# 323ampV1.net
KiCad netlist of a schematic drawn in EAGLE
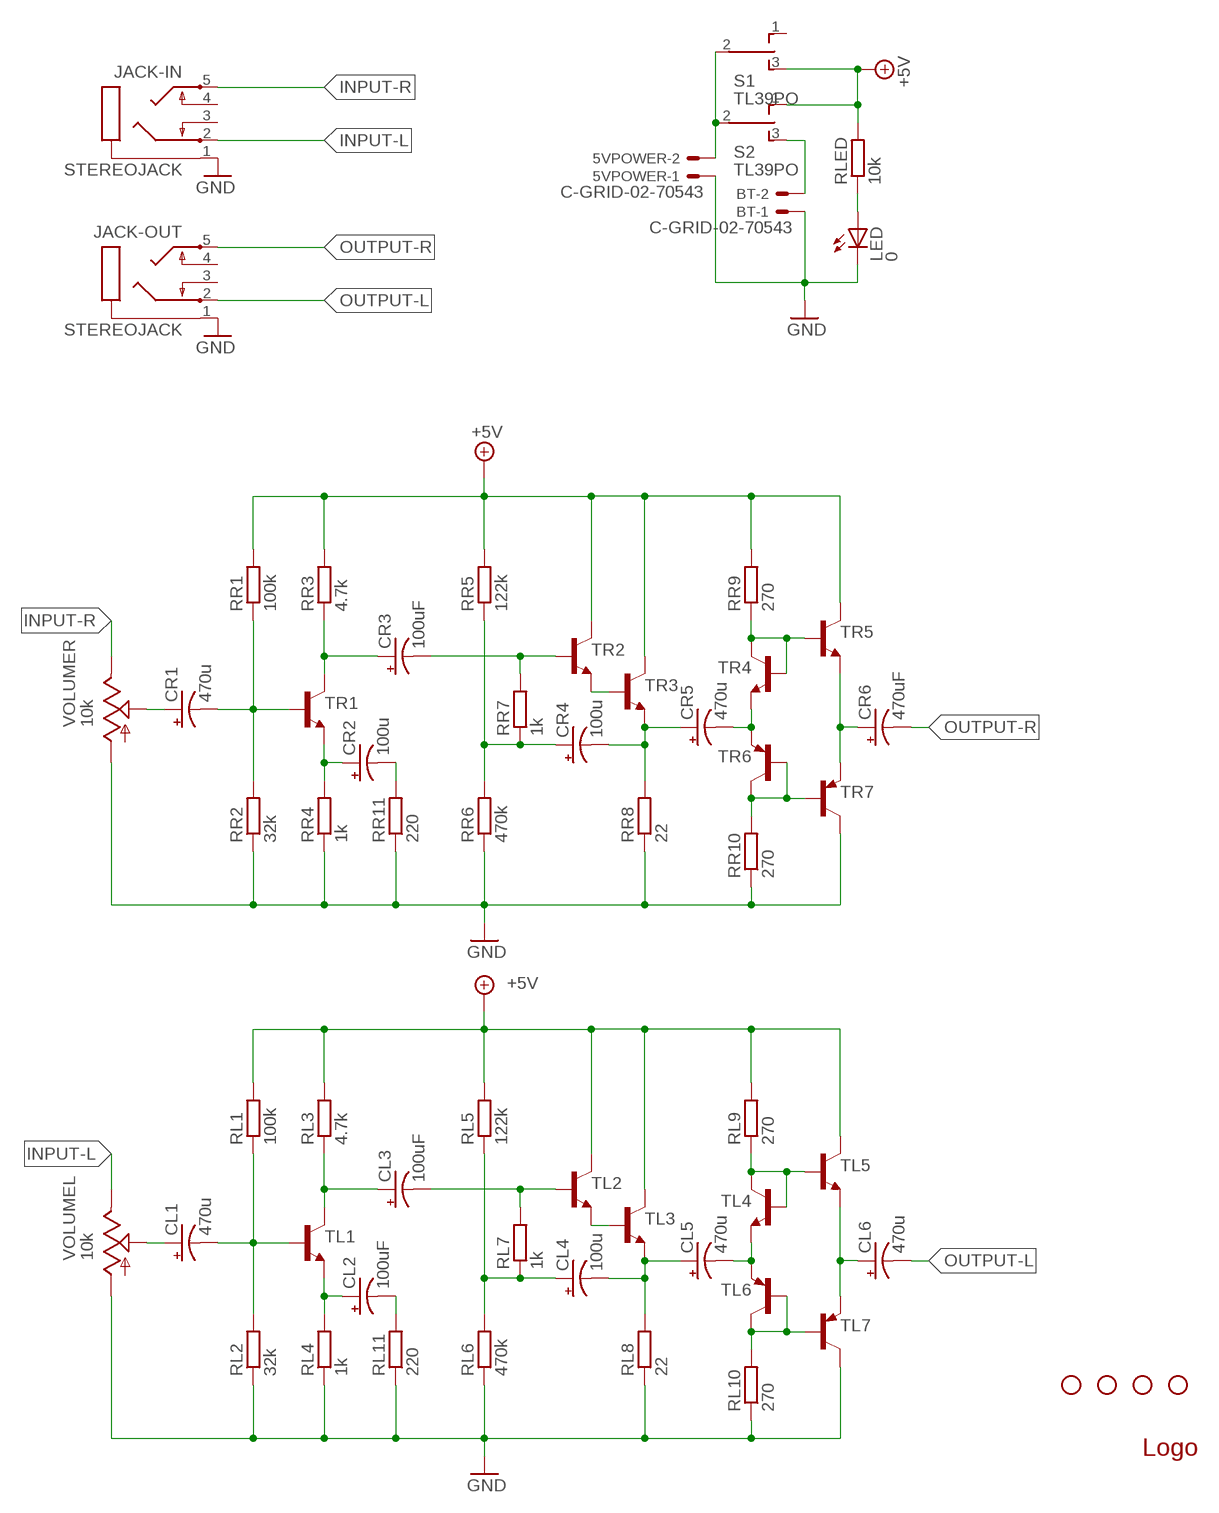
[diagram p0: schematic, sheet 1]

(export (version "E")
  (design (tool "Eeschema 10.0.6"))
  (components
    (comp (ref "5VPOWER")
      (value "C-GRID-02-70543")
      (footprint "eagle-import:70543-02")
      (libsource (lib "eagle-import") (part "C-GRID-02-70543"))
    )
    (comp (ref "BT")
      (value "C-GRID-02-70543")
      (footprint "eagle-import:70543-02")
      (libsource (lib "eagle-import") (part "C-GRID-02-70543"))
    )
    (comp (ref "CL1")
      (value "470u")
      (footprint "eagle-import:E2,5-6")
      (libsource (lib "eagle-import") (part "CPOL-USE2.5-6"))
    )
    (comp (ref "CL2")
      (value "100uF")
      (footprint "eagle-import:E2,5-6")
      (libsource (lib "eagle-import") (part "CPOL-USE2.5-6"))
    )
    (comp (ref "CL3")
      (value "100uF")
      (footprint "eagle-import:E2,5-6")
      (libsource (lib "eagle-import") (part "CPOL-USE2.5-6"))
    )
    (comp (ref "CL4")
      (value "100u")
      (footprint "eagle-import:E2,5-6")
      (libsource (lib "eagle-import") (part "CPOL-USE2.5-6"))
    )
    (comp (ref "CL5")
      (value "470u")
      (footprint "eagle-import:E2,5-6")
      (libsource (lib "eagle-import") (part "CPOL-USE2.5-6"))
    )
    (comp (ref "CL6")
      (value "470u")
      (footprint "eagle-import:E2,5-6")
      (libsource (lib "eagle-import") (part "CPOL-USE2.5-6"))
    )
    (comp (ref "CR1")
      (value "470u")
      (footprint "eagle-import:E2,5-6")
      (libsource (lib "eagle-import") (part "CPOL-USE2.5-6"))
    )
    (comp (ref "CR2")
      (value "100u")
      (footprint "eagle-import:E2,5-6")
      (libsource (lib "eagle-import") (part "CPOL-USE2.5-6"))
    )
    (comp (ref "CR3")
      (value "100uF")
      (footprint "eagle-import:E2,5-6")
      (libsource (lib "eagle-import") (part "CPOL-USE2.5-6"))
    )
    (comp (ref "CR4")
      (value "100u")
      (footprint "eagle-import:E2,5-6")
      (libsource (lib "eagle-import") (part "CPOL-USE2.5-6"))
    )
    (comp (ref "CR5")
      (value "470u")
      (footprint "eagle-import:E2,5-6")
      (libsource (lib "eagle-import") (part "CPOL-USE2.5-6"))
    )
    (comp (ref "CR6")
      (value "470uF")
      (footprint "eagle-import:E2,5-6")
      (libsource (lib "eagle-import") (part "CPOL-USE2.5-6"))
    )
    (comp (ref "JACK-IN")
      (value "STEREOJACK")
      (footprint "eagle-import:STX3100")
      (libsource (lib "eagle-import") (part "STEREOJACK"))
    )
    (comp (ref "JACK-OUT")
      (value "STEREOJACK")
      (footprint "eagle-import:STX3100")
      (libsource (lib "eagle-import") (part "STEREOJACK"))
    )
    (comp (ref "JP2")
      (value "STAND-OFF")
      (footprint "eagle-import:STAND-OFF")
      (libsource (lib "eagle-import") (part "STAND-OFF"))
    )
    (comp (ref "JP3")
      (value "STAND-OFF")
      (footprint "eagle-import:STAND-OFF")
      (libsource (lib "eagle-import") (part "STAND-OFF"))
    )
    (comp (ref "JP4")
      (value "STAND-OFF")
      (footprint "eagle-import:STAND-OFF")
      (libsource (lib "eagle-import") (part "STAND-OFF"))
    )
    (comp (ref "JP5")
      (value "STAND-OFF")
      (footprint "eagle-import:STAND-OFF")
      (libsource (lib "eagle-import") (part "STAND-OFF"))
    )
    (comp (ref "LED")
      (value "0")
      (footprint "eagle-import:LED3MM-MINUS")
      (libsource (lib "eagle-import") (part "LED-3MM-MINUS"))
    )
    (comp (ref "RL1")
      (value "100k")
      (footprint "eagle-import:0204_7")
      (libsource (lib "eagle-import") (part "R-EU_0204/7"))
    )
    (comp (ref "RL2")
      (value "32k")
      (footprint "eagle-import:0204_7")
      (libsource (lib "eagle-import") (part "R-EU_0204/7"))
    )
    (comp (ref "RL3")
      (value "4.7k")
      (footprint "eagle-import:0204_7")
      (libsource (lib "eagle-import") (part "R-EU_0204/7"))
    )
    (comp (ref "RL4")
      (value "1k")
      (footprint "eagle-import:0204_7")
      (libsource (lib "eagle-import") (part "R-EU_0204/7"))
    )
    (comp (ref "RL5")
      (value "122k")
      (footprint "eagle-import:0204_7")
      (libsource (lib "eagle-import") (part "R-EU_0204/7"))
    )
    (comp (ref "RL6")
      (value "470k")
      (footprint "eagle-import:0204_7")
      (libsource (lib "eagle-import") (part "R-EU_0204/7"))
    )
    (comp (ref "RL7")
      (value "1k")
      (footprint "eagle-import:0204_7")
      (libsource (lib "eagle-import") (part "R-EU_0204/7"))
    )
    (comp (ref "RL8")
      (value "22")
      (footprint "eagle-import:0204_7")
      (libsource (lib "eagle-import") (part "R-EU_0204/7"))
    )
    (comp (ref "RL9")
      (value "270")
      (footprint "eagle-import:0204_7")
      (libsource (lib "eagle-import") (part "R-EU_0204/7"))
    )
    (comp (ref "RL10")
      (value "270")
      (footprint "eagle-import:0204_7")
      (libsource (lib "eagle-import") (part "R-EU_0204/7"))
    )
    (comp (ref "RL11")
      (value "220")
      (footprint "eagle-import:0204_7")
      (libsource (lib "eagle-import") (part "R-EU_0204/7"))
    )
    (comp (ref "RLED")
      (value "10k")
      (footprint "eagle-import:0204_7")
      (libsource (lib "eagle-import") (part "R-EU_0204/7"))
    )
    (comp (ref "RR1")
      (value "100k")
      (footprint "eagle-import:0204_7")
      (libsource (lib "eagle-import") (part "R-EU_0204/7"))
    )
    (comp (ref "RR2")
      (value "32k")
      (footprint "eagle-import:0204_7")
      (libsource (lib "eagle-import") (part "R-EU_0204/7"))
    )
    (comp (ref "RR3")
      (value "4.7k")
      (footprint "eagle-import:0204_7")
      (libsource (lib "eagle-import") (part "R-EU_0204/7"))
    )
    (comp (ref "RR4")
      (value "1k")
      (footprint "eagle-import:0204_7")
      (libsource (lib "eagle-import") (part "R-EU_0204/7"))
    )
    (comp (ref "RR5")
      (value "122k")
      (footprint "eagle-import:0204_7")
      (libsource (lib "eagle-import") (part "R-EU_0204/7"))
    )
    (comp (ref "RR6")
      (value "470k")
      (footprint "eagle-import:0204_7")
      (libsource (lib "eagle-import") (part "R-EU_0204/7"))
    )
    (comp (ref "RR7")
      (value "1k")
      (footprint "eagle-import:0204_7")
      (libsource (lib "eagle-import") (part "R-EU_0204/7"))
    )
    (comp (ref "RR8")
      (value "22")
      (footprint "eagle-import:0204_7")
      (libsource (lib "eagle-import") (part "R-EU_0204/7"))
    )
    (comp (ref "RR9")
      (value "270")
      (footprint "eagle-import:0204_7")
      (libsource (lib "eagle-import") (part "R-EU_0204/7"))
    )
    (comp (ref "RR10")
      (value "270")
      (footprint "eagle-import:0204_7")
      (libsource (lib "eagle-import") (part "R-EU_0204/7"))
    )
    (comp (ref "RR11")
      (value "220")
      (footprint "eagle-import:0204_7")
      (libsource (lib "eagle-import") (part "R-EU_0204/7"))
    )
    (comp (ref "S1")
      (value "TL39PO")
      (footprint "eagle-import:TL3XPO")
      (libsource (lib "eagle-import") (part "TL39PO"))
    )
    (comp (ref "S2")
      (value "TL39PO")
      (footprint "eagle-import:TL3XPO")
      (libsource (lib "eagle-import") (part "TL39PO"))
    )
    (comp (ref "TL1")
      (value "2N4401-NPN-TO92-EBC")
      (footprint "eagle-import:TO92-EBC")
      (libsource (lib "eagle-import") (part "-NPN-TO92-EBC2N4401"))
    )
    (comp (ref "TL2")
      (value "2N4401-NPN-TO92-EBC")
      (footprint "eagle-import:TO92-EBC")
      (libsource (lib "eagle-import") (part "-NPN-TO92-EBC2N4401"))
    )
    (comp (ref "TL3")
      (value "2N4401-NPN-TO92-EBC")
      (footprint "eagle-import:TO92-EBC")
      (libsource (lib "eagle-import") (part "-NPN-TO92-EBC2N4401"))
    )
    (comp (ref "TL4")
      (value "2N4401-NPN-TO92-EBC")
      (footprint "eagle-import:TO92-EBC")
      (libsource (lib "eagle-import") (part "-NPN-TO92-EBC2N4401"))
    )
    (comp (ref "TL5")
      (value "2N4401-NPN-TO92-EBC")
      (footprint "eagle-import:TO92-EBC")
      (libsource (lib "eagle-import") (part "-NPN-TO92-EBC2N4401"))
    )
    (comp (ref "TL6")
      (value "2N4403-PNP-TO92-EBC")
      (footprint "eagle-import:TO92-EBC")
      (libsource (lib "eagle-import") (part "-PNP-TO92-EBC2N4403"))
    )
    (comp (ref "TL7")
      (value "2N4403-PNP-TO92-EBC")
      (footprint "eagle-import:TO92-EBC")
      (libsource (lib "eagle-import") (part "-PNP-TO92-EBC2N4403"))
    )
    (comp (ref "TR1")
      (value "2N4401-NPN-TO92-EBC")
      (footprint "eagle-import:TO92-EBC")
      (libsource (lib "eagle-import") (part "-NPN-TO92-EBC2N4401"))
    )
    (comp (ref "TR2")
      (value "2N4401-NPN-TO92-EBC")
      (footprint "eagle-import:TO92-EBC")
      (libsource (lib "eagle-import") (part "-NPN-TO92-EBC2N4401"))
    )
    (comp (ref "TR3")
      (value "2N4401-NPN-TO92-EBC")
      (footprint "eagle-import:TO92-EBC")
      (libsource (lib "eagle-import") (part "-NPN-TO92-EBC2N4401"))
    )
    (comp (ref "TR4")
      (value "2N4401-NPN-TO92-EBC")
      (footprint "eagle-import:TO92-EBC")
      (libsource (lib "eagle-import") (part "-NPN-TO92-EBC2N4401"))
    )
    (comp (ref "TR5")
      (value "2N4401-NPN-TO92-EBC")
      (footprint "eagle-import:TO92-EBC")
      (libsource (lib "eagle-import") (part "-NPN-TO92-EBC2N4401"))
    )
    (comp (ref "TR6")
      (value "2N4403-PNP-TO92-EBC")
      (footprint "eagle-import:TO92-EBC")
      (libsource (lib "eagle-import") (part "-PNP-TO92-EBC2N4403"))
    )
    (comp (ref "TR7")
      (value "2N4403-PNP-TO92-EBC")
      (footprint "eagle-import:TO92-EBC")
      (libsource (lib "eagle-import") (part "-PNP-TO92-EBC2N4403"))
    )
    (comp (ref "U$1")
      (value "OSHW-LOGO-OUTLINE")
      (footprint "eagle-import:OSHW-LOGO-OUTLINE")
      (libsource (lib "eagle-import") (part "OSHW-LOGO-OUTLINE"))
    )
    (comp (ref "VOLUME")
      (value "10k")
      (footprint "eagle-import:ALPS_RK0971221Z0X")
      (libsource (lib "eagle-import") (part "ALPS_RK0971221Z0N"))
    )
  )
  (nets
    (net (code "1") (name "+5V") (class "Default")
      (node (ref "RL1") (pin "2") (pinfunction "2_2") (pintype "passive"))
      (node (ref "RL3") (pin "2") (pinfunction "2_2") (pintype "passive"))
      (node (ref "RL5") (pin "2") (pinfunction "2_2") (pintype "passive"))
      (node (ref "RL9") (pin "2") (pinfunction "2_2") (pintype "passive"))
      (node (ref "RLED") (pin "2") (pinfunction "2_2") (pintype "passive"))
      (node (ref "RR1") (pin "2") (pinfunction "2_2") (pintype "passive"))
      (node (ref "RR3") (pin "2") (pinfunction "2_2") (pintype "passive"))
      (node (ref "RR5") (pin "2") (pinfunction "2_2") (pintype "passive"))
      (node (ref "RR9") (pin "2") (pinfunction "2_2") (pintype "passive"))
      (node (ref "S1") (pin "3") (pinfunction "S_3") (pintype "passive"))
      (node (ref "S2") (pin "1") (pinfunction "O_1") (pintype "passive"))
      (node (ref "TL2") (pin "C") (pinfunction "C_C") (pintype "passive"))
      (node (ref "TL3") (pin "C") (pinfunction "C_C") (pintype "passive"))
      (node (ref "TL5") (pin "C") (pinfunction "C_C") (pintype "passive"))
      (node (ref "TR2") (pin "C") (pinfunction "C_C") (pintype "passive"))
      (node (ref "TR3") (pin "C") (pinfunction "C_C") (pintype "passive"))
      (node (ref "TR5") (pin "C") (pinfunction "C_C") (pintype "passive"))
    )
    (net (code "2") (name "GND") (class "Default")
      (node (ref "5VPOWER") (pin "1") (pinfunction "S_1") (pintype "passive"))
      (node (ref "BT") (pin "1") (pinfunction "S_1") (pintype "passive"))
      (node (ref "JACK-IN") (pin "1") (pinfunction "1_1") (pintype "passive"))
      (node (ref "JACK-OUT") (pin "1") (pinfunction "1_1") (pintype "passive"))
      (node (ref "LED") (pin "K") (pinfunction "C_K") (pintype "passive"))
      (node (ref "RL10") (pin "1") (pinfunction "1_1") (pintype "passive"))
      (node (ref "RL11") (pin "1") (pinfunction "1_1") (pintype "passive"))
      (node (ref "RL2") (pin "1") (pinfunction "1_1") (pintype "passive"))
      (node (ref "RL4") (pin "1") (pinfunction "1_1") (pintype "passive"))
      (node (ref "RL6") (pin "1") (pinfunction "1_1") (pintype "passive"))
      (node (ref "RL8") (pin "1") (pinfunction "1_1") (pintype "passive"))
      (node (ref "RR10") (pin "1") (pinfunction "1_1") (pintype "passive"))
      (node (ref "RR11") (pin "1") (pinfunction "1_1") (pintype "passive"))
      (node (ref "RR2") (pin "1") (pinfunction "1_1") (pintype "passive"))
      (node (ref "RR4") (pin "1") (pinfunction "1_1") (pintype "passive"))
      (node (ref "RR6") (pin "1") (pinfunction "1_1") (pintype "passive"))
      (node (ref "RR8") (pin "1") (pinfunction "1_1") (pintype "passive"))
      (node (ref "TL7") (pin "C") (pinfunction "C_C") (pintype "passive"))
      (node (ref "TR7") (pin "C") (pinfunction "C_C") (pintype "passive"))
      (node (ref "VOLUME") (pin "G1") (pinfunction "1_G1") (pintype "passive"))
      (node (ref "VOLUME") (pin "G2") (pinfunction "1_G2") (pintype "passive"))
    )
    (net (code "3") (name "INPUT-L") (class "Default")
      (node (ref "JACK-IN") (pin "2") (pinfunction "2_2") (pintype "passive"))
      (node (ref "VOLUME") (pin "I1") (pinfunction "3_I1") (pintype "passive"))
    )
    (net (code "4") (name "INPUT-R") (class "Default")
      (node (ref "JACK-IN") (pin "5") (pinfunction "5_5") (pintype "passive"))
      (node (ref "VOLUME") (pin "I2") (pinfunction "3_I2") (pintype "passive"))
    )
    (net (code "5") (name "Net-(5VPOWERB-S)") (class "Default")
      (node (ref "5VPOWER") (pin "2") (pinfunction "S_2") (pintype "passive"))
      (node (ref "S1") (pin "2") (pinfunction "P_2") (pintype "passive"))
      (node (ref "S2") (pin "2") (pinfunction "P_2") (pintype "passive"))
    )
    (net (code "6") (name "Net-(BTB-S)") (class "Default")
      (node (ref "BT") (pin "2") (pinfunction "S_2") (pintype "passive"))
      (node (ref "S2") (pin "3") (pinfunction "S_3") (pintype "passive"))
    )
    (net (code "7") (name "Net-(CL1-Pad-)") (class "Default")
      (node (ref "CL1") (pin "-") (pinfunction "-_-") (pintype "passive"))
      (node (ref "RL1") (pin "1") (pinfunction "1_1") (pintype "passive"))
      (node (ref "RL2") (pin "2") (pinfunction "2_2") (pintype "passive"))
      (node (ref "TL1") (pin "B") (pinfunction "B_B") (pintype "passive"))
    )
    (net (code "8") (name "Net-(CL2-Pad+)") (class "Default")
      (node (ref "CL2") (pin "+") (pinfunction "+_+") (pintype "passive"))
      (node (ref "RL4") (pin "2") (pinfunction "2_2") (pintype "passive"))
      (node (ref "TL1") (pin "E") (pinfunction "E_E") (pintype "passive"))
    )
    (net (code "9") (name "Net-(CL2-Pad-)") (class "Default")
      (node (ref "CL2") (pin "-") (pinfunction "-_-") (pintype "passive"))
      (node (ref "RL11") (pin "2") (pinfunction "2_2") (pintype "passive"))
    )
    (net (code "10") (name "Net-(CL3-Pad+)") (class "Default")
      (node (ref "CL3") (pin "+") (pinfunction "+_+") (pintype "passive"))
      (node (ref "RL3") (pin "1") (pinfunction "1_1") (pintype "passive"))
      (node (ref "TL1") (pin "C") (pinfunction "C_C") (pintype "passive"))
    )
    (net (code "11") (name "Net-(CL3-Pad-)") (class "Default")
      (node (ref "CL3") (pin "-") (pinfunction "-_-") (pintype "passive"))
      (node (ref "RL7") (pin "2") (pinfunction "2_2") (pintype "passive"))
      (node (ref "TL2") (pin "B") (pinfunction "B_B") (pintype "passive"))
    )
    (net (code "12") (name "Net-(CL4-Pad+)") (class "Default")
      (node (ref "CL4") (pin "+") (pinfunction "+_+") (pintype "passive"))
      (node (ref "RL5") (pin "1") (pinfunction "1_1") (pintype "passive"))
      (node (ref "RL6") (pin "2") (pinfunction "2_2") (pintype "passive"))
      (node (ref "RL7") (pin "1") (pinfunction "1_1") (pintype "passive"))
    )
    (net (code "13") (name "Net-(CL4-Pad-)") (class "Default")
      (node (ref "CL4") (pin "-") (pinfunction "-_-") (pintype "passive"))
      (node (ref "CL5") (pin "+") (pinfunction "+_+") (pintype "passive"))
      (node (ref "RL8") (pin "2") (pinfunction "2_2") (pintype "passive"))
      (node (ref "TL3") (pin "E") (pinfunction "E_E") (pintype "passive"))
    )
    (net (code "14") (name "Net-(CL5-Pad-)") (class "Default")
      (node (ref "CL5") (pin "-") (pinfunction "-_-") (pintype "passive"))
      (node (ref "TL4") (pin "E") (pinfunction "E_E") (pintype "passive"))
      (node (ref "TL6") (pin "E") (pinfunction "E_E") (pintype "passive"))
    )
    (net (code "15") (name "Net-(CL6-Pad+)") (class "Default")
      (node (ref "CL6") (pin "+") (pinfunction "+_+") (pintype "passive"))
      (node (ref "TL5") (pin "E") (pinfunction "E_E") (pintype "passive"))
      (node (ref "TL7") (pin "E") (pinfunction "E_E") (pintype "passive"))
    )
    (net (code "16") (name "Net-(CR1-Pad-)") (class "Default")
      (node (ref "CR1") (pin "-") (pinfunction "-_-") (pintype "passive"))
      (node (ref "RR1") (pin "1") (pinfunction "1_1") (pintype "passive"))
      (node (ref "RR2") (pin "2") (pinfunction "2_2") (pintype "passive"))
      (node (ref "TR1") (pin "B") (pinfunction "B_B") (pintype "passive"))
    )
    (net (code "17") (name "Net-(CR2-Pad+)") (class "Default")
      (node (ref "CR2") (pin "+") (pinfunction "+_+") (pintype "passive"))
      (node (ref "RR4") (pin "2") (pinfunction "2_2") (pintype "passive"))
      (node (ref "TR1") (pin "E") (pinfunction "E_E") (pintype "passive"))
    )
    (net (code "18") (name "Net-(CR2-Pad-)") (class "Default")
      (node (ref "CR2") (pin "-") (pinfunction "-_-") (pintype "passive"))
      (node (ref "RR11") (pin "2") (pinfunction "2_2") (pintype "passive"))
    )
    (net (code "19") (name "Net-(CR3-Pad+)") (class "Default")
      (node (ref "CR3") (pin "+") (pinfunction "+_+") (pintype "passive"))
      (node (ref "RR3") (pin "1") (pinfunction "1_1") (pintype "passive"))
      (node (ref "TR1") (pin "C") (pinfunction "C_C") (pintype "passive"))
    )
    (net (code "20") (name "Net-(CR3-Pad-)") (class "Default")
      (node (ref "CR3") (pin "-") (pinfunction "-_-") (pintype "passive"))
      (node (ref "RR7") (pin "2") (pinfunction "2_2") (pintype "passive"))
      (node (ref "TR2") (pin "B") (pinfunction "B_B") (pintype "passive"))
    )
    (net (code "21") (name "Net-(CR4-Pad+)") (class "Default")
      (node (ref "CR4") (pin "+") (pinfunction "+_+") (pintype "passive"))
      (node (ref "RR5") (pin "1") (pinfunction "1_1") (pintype "passive"))
      (node (ref "RR6") (pin "2") (pinfunction "2_2") (pintype "passive"))
      (node (ref "RR7") (pin "1") (pinfunction "1_1") (pintype "passive"))
    )
    (net (code "22") (name "Net-(CR4-Pad-)") (class "Default")
      (node (ref "CR4") (pin "-") (pinfunction "-_-") (pintype "passive"))
      (node (ref "CR5") (pin "+") (pinfunction "+_+") (pintype "passive"))
      (node (ref "RR8") (pin "2") (pinfunction "2_2") (pintype "passive"))
      (node (ref "TR3") (pin "E") (pinfunction "E_E") (pintype "passive"))
    )
    (net (code "23") (name "Net-(CR5-Pad-)") (class "Default")
      (node (ref "CR5") (pin "-") (pinfunction "-_-") (pintype "passive"))
      (node (ref "TR4") (pin "E") (pinfunction "E_E") (pintype "passive"))
      (node (ref "TR6") (pin "E") (pinfunction "E_E") (pintype "passive"))
    )
    (net (code "24") (name "Net-(CR6-Pad+)") (class "Default")
      (node (ref "CR6") (pin "+") (pinfunction "+_+") (pintype "passive"))
      (node (ref "TR5") (pin "E") (pinfunction "E_E") (pintype "passive"))
      (node (ref "TR7") (pin "E") (pinfunction "E_E") (pintype "passive"))
    )
    (net (code "25") (name "Net-(LED-PadA)") (class "Default")
      (node (ref "LED") (pin "A") (pinfunction "A_A") (pintype "passive"))
      (node (ref "RLED") (pin "1") (pinfunction "1_1") (pintype "passive"))
    )
    (net (code "26") (name "Net-(RL9-Pad1)") (class "Default")
      (node (ref "RL9") (pin "1") (pinfunction "1_1") (pintype "passive"))
      (node (ref "TL4") (pin "B") (pinfunction "B_B") (pintype "passive"))
      (node (ref "TL4") (pin "C") (pinfunction "C_C") (pintype "passive"))
      (node (ref "TL5") (pin "B") (pinfunction "B_B") (pintype "passive"))
    )
    (net (code "27") (name "Net-(RL10-Pad2)") (class "Default")
      (node (ref "RL10") (pin "2") (pinfunction "2_2") (pintype "passive"))
      (node (ref "TL6") (pin "B") (pinfunction "B_B") (pintype "passive"))
      (node (ref "TL6") (pin "C") (pinfunction "C_C") (pintype "passive"))
      (node (ref "TL7") (pin "B") (pinfunction "B_B") (pintype "passive"))
    )
    (net (code "28") (name "Net-(RR9-Pad1)") (class "Default")
      (node (ref "RR9") (pin "1") (pinfunction "1_1") (pintype "passive"))
      (node (ref "TR4") (pin "B") (pinfunction "B_B") (pintype "passive"))
      (node (ref "TR4") (pin "C") (pinfunction "C_C") (pintype "passive"))
      (node (ref "TR5") (pin "B") (pinfunction "B_B") (pintype "passive"))
    )
    (net (code "29") (name "Net-(RR10-Pad2)") (class "Default")
      (node (ref "RR10") (pin "2") (pinfunction "2_2") (pintype "passive"))
      (node (ref "TR6") (pin "B") (pinfunction "B_B") (pintype "passive"))
      (node (ref "TR6") (pin "C") (pinfunction "C_C") (pintype "passive"))
      (node (ref "TR7") (pin "B") (pinfunction "B_B") (pintype "passive"))
    )
    (net (code "30") (name "Net-(TL2-PadE)") (class "Default")
      (node (ref "TL2") (pin "E") (pinfunction "E_E") (pintype "passive"))
      (node (ref "TL3") (pin "B") (pinfunction "B_B") (pintype "passive"))
    )
    (net (code "31") (name "Net-(TR2-PadE)") (class "Default")
      (node (ref "TR2") (pin "E") (pinfunction "E_E") (pintype "passive"))
      (node (ref "TR3") (pin "B") (pinfunction "B_B") (pintype "passive"))
    )
    (net (code "32") (name "Net-(VOLUMEB-2)") (class "Default")
      (node (ref "CL1") (pin "+") (pinfunction "+_+") (pintype "passive"))
      (node (ref "VOLUME") (pin "O1") (pinfunction "2_O1") (pintype "passive"))
    )
    (net (code "33") (name "Net-(VOLUMEC-2)") (class "Default")
      (node (ref "CR1") (pin "+") (pinfunction "+_+") (pintype "passive"))
      (node (ref "VOLUME") (pin "O2") (pinfunction "2_O2") (pintype "passive"))
    )
    (net (code "34") (name "OUTPUT-L") (class "Default")
      (node (ref "CL6") (pin "-") (pinfunction "-_-") (pintype "passive"))
      (node (ref "JACK-OUT") (pin "2") (pinfunction "2_2") (pintype "passive"))
    )
    (net (code "35") (name "OUTPUT-R") (class "Default")
      (node (ref "CR6") (pin "-") (pinfunction "-_-") (pintype "passive"))
      (node (ref "JACK-OUT") (pin "5") (pinfunction "5_5") (pintype "passive"))
    )
    (net (code "36") (name "unconnected-(JACK-IN-Pad3)") (class "Default")
      (node (ref "JACK-IN") (pin "3") (pinfunction "3_3") (pintype "passive"))
    )
    (net (code "37") (name "unconnected-(JACK-IN-Pad4)") (class "Default")
      (node (ref "JACK-IN") (pin "4") (pinfunction "4_4") (pintype "passive"))
    )
    (net (code "38") (name "unconnected-(JACK-OUT-Pad3)") (class "Default")
      (node (ref "JACK-OUT") (pin "3") (pinfunction "3_3") (pintype "passive"))
    )
    (net (code "39") (name "unconnected-(JACK-OUT-Pad4)") (class "Default")
      (node (ref "JACK-OUT") (pin "4") (pinfunction "4_4") (pintype "passive"))
    )
    (net (code "40") (name "unconnected-(S1-O-Pad1)") (class "Default")
      (node (ref "S1") (pin "1") (pinfunction "O_1") (pintype "passive"))
    )
  )
)
